# Environment_Sensor.net
KiCad netlist of a schematic drawn in EAGLE
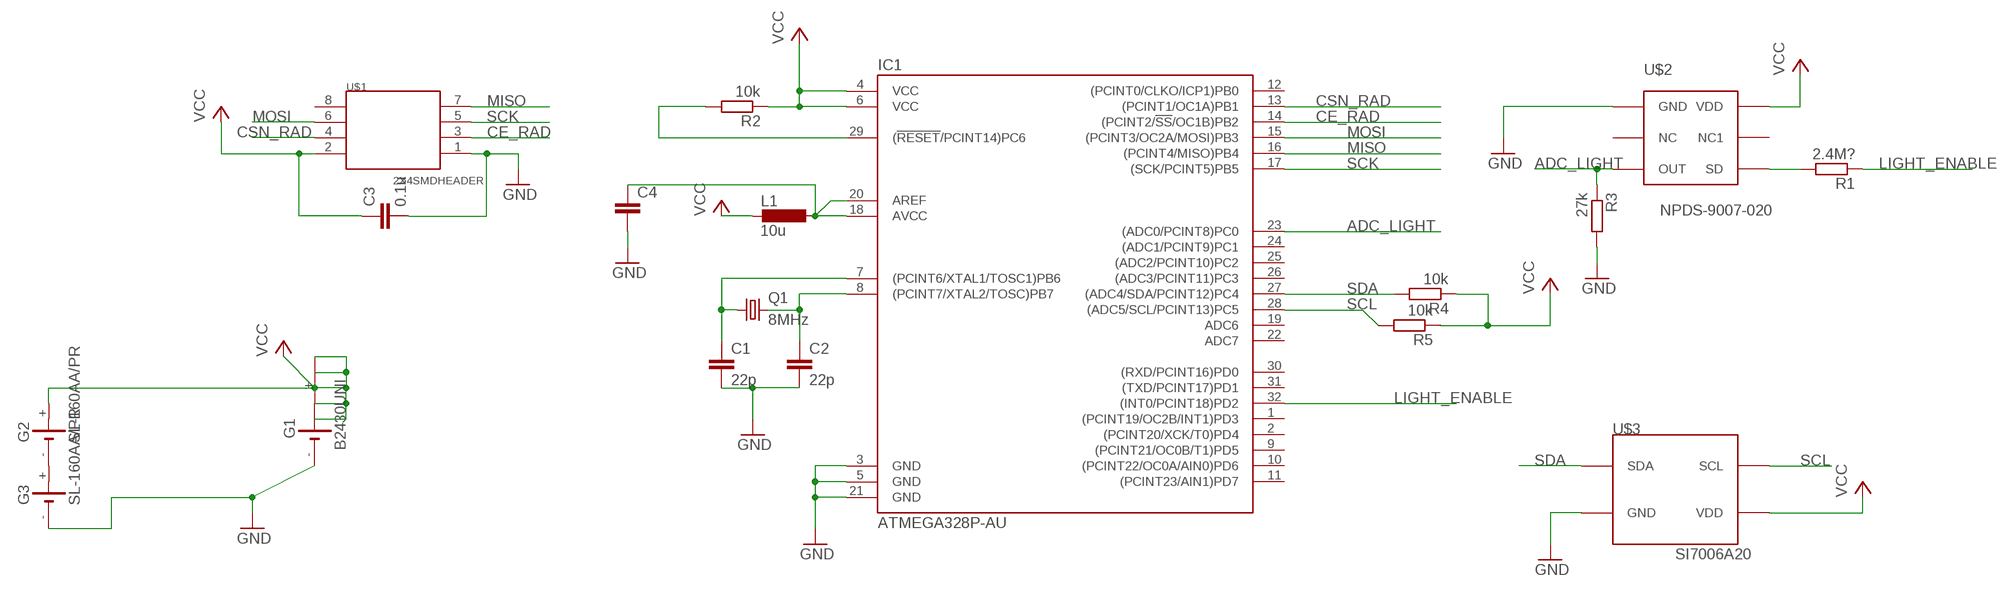
[diagram p0: schematic, sheet 1]

(export (version "E")
  (design (tool "Eeschema 10.0.6"))
  (components
    (comp (ref "C1")
      (value "22p")
      (footprint "eagle-import:C1206K")
      (libsource (lib "eagle-import") (part "C-EUC1206K"))
    )
    (comp (ref "C2")
      (value "22p")
      (footprint "eagle-import:C1206K")
      (libsource (lib "eagle-import") (part "C-EUC1206K"))
    )
    (comp (ref "C3")
      (value "0.1u")
      (footprint "eagle-import:C1206K")
      (libsource (lib "eagle-import") (part "C-EUC1206K"))
    )
    (comp (ref "C4")
      (value "C-EUC1206")
      (footprint "eagle-import:C1206")
      (libsource (lib "eagle-import") (part "C-EUC1206"))
    )
    (comp (ref "G1")
      (value "B2430UNI")
      (footprint "eagle-import:B2430UNI")
      (libsource (lib "eagle-import") (part "B2430UNI"))
    )
    (comp (ref "G2")
      (value "SL-160AA/PR")
      (footprint "eagle-import:SL-160AA_PR")
      (libsource (lib "eagle-import") (part "SL-160AA/PR"))
    )
    (comp (ref "G3")
      (value "SL-160AA/PR")
      (footprint "eagle-import:SL-160AA_PR")
      (libsource (lib "eagle-import") (part "SL-160AA/PR"))
    )
    (comp (ref "IC1")
      (value "ATMEGA328P-AU")
      (footprint "eagle-import:TQFP32-08")
      (libsource (lib "eagle-import") (part "ATMEGA328P-AU"))
    )
    (comp (ref "L1")
      (value "10u")
      (footprint "eagle-import:L3216C")
      (libsource (lib "eagle-import") (part "L-EUL3216C"))
    )
    (comp (ref "Q1")
      (value "8MHz")
      (footprint "eagle-import:HC49UP")
      (libsource (lib "eagle-import") (part "CRYSTALHC49UP"))
    )
    (comp (ref "R1")
      (value "2.4M?")
      (footprint "eagle-import:R1206")
      (libsource (lib "eagle-import") (part "R-EU_R1206"))
    )
    (comp (ref "R2")
      (value "10k")
      (footprint "eagle-import:R1206")
      (libsource (lib "eagle-import") (part "R-EU_R1206"))
    )
    (comp (ref "R3")
      (value "27k")
      (footprint "eagle-import:R1206")
      (libsource (lib "eagle-import") (part "R-EU_R1206"))
    )
    (comp (ref "R4")
      (value "10k")
      (footprint "eagle-import:R1206")
      (libsource (lib "eagle-import") (part "R-EU_R1206"))
    )
    (comp (ref "R5")
      (value "10k")
      (footprint "eagle-import:R1206")
      (libsource (lib "eagle-import") (part "R-EU_R1206"))
    )
    (comp (ref "U$1")
      (value "2X4SMDHEADER")
      (footprint "eagle-import:TSM-110-XX-XXX-DV")
      (libsource (lib "eagle-import") (part "2X4SMDHEADER"))
    )
    (comp (ref "U$2")
      (value "NPDS-9007-020")
      (footprint "eagle-import:APDS-9007")
      (libsource (lib "eagle-import") (part "NPDS-9007-020"))
    )
    (comp (ref "U$3")
      (value "SI7006A20")
      (footprint "eagle-import:3X3DFN")
      (libsource (lib "eagle-import") (part "SI7006A20"))
    )
  )
  (nets
    (net (code "1") (name "/ADC_LIGHT") (class "Default")
      (node (ref "IC1") (pin "23") (pinfunction "(ADC0/PCINT8)PC0_23") (pintype "bidirectional"))
      (node (ref "R3") (pin "1") (pinfunction "1_1") (pintype "passive"))
      (node (ref "U$2") (pin "P$3") (pinfunction "OUT_P$3") (pintype "bidirectional"))
    )
    (net (code "2") (name "/CE_RAD") (class "Default")
      (node (ref "IC1") (pin "14") (pinfunction "(PCINT2/~{SS}/OC1B)PB2_14") (pintype "bidirectional"))
      (node (ref "U$1") (pin "3") (pinfunction "3_3") (pintype "bidirectional"))
    )
    (net (code "3") (name "/CSN_RAD") (class "Default")
      (node (ref "IC1") (pin "13") (pinfunction "(PCINT1/OC1A)PB1_13") (pintype "bidirectional"))
      (node (ref "U$1") (pin "4") (pinfunction "4_4") (pintype "bidirectional"))
    )
    (net (code "4") (name "/LIGHT_ENABLE") (class "Default")
      (node (ref "IC1") (pin "32") (pinfunction "(INT0/PCINT18)PD2_32") (pintype "bidirectional"))
      (node (ref "R1") (pin "1") (pinfunction "1_1") (pintype "passive"))
    )
    (net (code "5") (name "/MISO") (class "Default")
      (node (ref "IC1") (pin "16") (pinfunction "(PCINT4/MISO)PB4_16") (pintype "bidirectional"))
      (node (ref "U$1") (pin "7") (pinfunction "7_7") (pintype "bidirectional"))
    )
    (net (code "6") (name "/MOSI") (class "Default")
      (node (ref "IC1") (pin "15") (pinfunction "(PCINT3/OC2A/MOSI)PB3_15") (pintype "bidirectional"))
      (node (ref "U$1") (pin "6") (pinfunction "6_6") (pintype "bidirectional"))
    )
    (net (code "7") (name "/SCK") (class "Default")
      (node (ref "IC1") (pin "17") (pinfunction "(SCK/PCINT5)PB5_17") (pintype "bidirectional"))
      (node (ref "U$1") (pin "5") (pinfunction "5_5") (pintype "bidirectional"))
    )
    (net (code "8") (name "/SCL") (class "Default")
      (node (ref "IC1") (pin "28") (pinfunction "(ADC5/SCL/PCINT13)PC5_28") (pintype "bidirectional"))
      (node (ref "R5") (pin "2") (pinfunction "2_2") (pintype "passive"))
      (node (ref "U$3") (pin "P$6") (pinfunction "SCL_P$6") (pintype "bidirectional"))
    )
    (net (code "9") (name "/SDA") (class "Default")
      (node (ref "IC1") (pin "27") (pinfunction "(ADC4/SDA/PCINT12)PC4_27") (pintype "bidirectional"))
      (node (ref "R4") (pin "2") (pinfunction "2_2") (pintype "passive"))
      (node (ref "U$3") (pin "P$1") (pinfunction "SDA_P$1") (pintype "bidirectional"))
    )
    (net (code "10") (name "GND") (class "Default")
      (node (ref "C1") (pin "2") (pinfunction "2_2") (pintype "passive"))
      (node (ref "C2") (pin "2") (pinfunction "2_2") (pintype "passive"))
      (node (ref "C3") (pin "2") (pinfunction "2_2") (pintype "passive"))
      (node (ref "C4") (pin "2") (pinfunction "2_2") (pintype "passive"))
      (node (ref "G1") (pin "-") (pinfunction "-_-") (pintype "passive"))
      (node (ref "G3") (pin "-") (pinfunction "-_-") (pintype "passive"))
      (node (ref "IC1") (pin "21") (pinfunction "GND_21") (pintype "bidirectional"))
      (node (ref "IC1") (pin "3") (pinfunction "GND_3") (pintype "bidirectional"))
      (node (ref "IC1") (pin "5") (pinfunction "GND_5") (pintype "bidirectional"))
      (node (ref "R3") (pin "2") (pinfunction "2_2") (pintype "passive"))
      (node (ref "U$1") (pin "1") (pinfunction "1_1") (pintype "bidirectional"))
      (node (ref "U$2") (pin "P$1") (pinfunction "GND_P$1") (pintype "bidirectional"))
      (node (ref "U$3") (pin "P$2") (pinfunction "GND_P$2") (pintype "bidirectional"))
    )
    (net (code "11") (name "Net-(G2-Pad-)") (class "Default")
      (node (ref "G2") (pin "-") (pinfunction "-_-") (pintype "passive"))
      (node (ref "G3") (pin "+") (pinfunction "+_+") (pintype "passive"))
    )
    (net (code "12") (name "Net-(IC1-(PCINT6{slash}XTAL1{slash}TOSC1)PB6)") (class "Default")
      (node (ref "C1") (pin "1") (pinfunction "1_1") (pintype "passive"))
      (node (ref "IC1") (pin "7") (pinfunction "(PCINT6/XTAL1/TOSC1)PB6_7") (pintype "bidirectional"))
      (node (ref "Q1") (pin "1") (pinfunction "1_1") (pintype "passive"))
    )
    (net (code "13") (name "Net-(IC1-(PCINT7{slash}XTAL2{slash}TOSC)PB7)") (class "Default")
      (node (ref "C2") (pin "1") (pinfunction "1_1") (pintype "passive"))
      (node (ref "IC1") (pin "8") (pinfunction "(PCINT7/XTAL2/TOSC)PB7_8") (pintype "bidirectional"))
      (node (ref "Q1") (pin "2") (pinfunction "2_2") (pintype "passive"))
    )
    (net (code "14") (name "Net-(IC1-(~{RESET}{slash}PCINT14)PC6)") (class "Default")
      (node (ref "IC1") (pin "29") (pinfunction "(~{RESET}/PCINT14)PC6_29") (pintype "bidirectional"))
      (node (ref "R2") (pin "2") (pinfunction "2_2") (pintype "passive"))
    )
    (net (code "15") (name "Net-(IC1-AREF)") (class "Default")
      (node (ref "C4") (pin "1") (pinfunction "1_1") (pintype "passive"))
      (node (ref "IC1") (pin "18") (pinfunction "AVCC_18") (pintype "bidirectional"))
      (node (ref "IC1") (pin "20") (pinfunction "AREF_20") (pintype "bidirectional"))
      (node (ref "L1") (pin "1") (pinfunction "1_1") (pintype "passive"))
    )
    (net (code "16") (name "Net-(U$2-SD)") (class "Default")
      (node (ref "R1") (pin "2") (pinfunction "2_2") (pintype "passive"))
      (node (ref "U$2") (pin "P$6") (pinfunction "SD_P$6") (pintype "bidirectional"))
    )
    (net (code "17") (name "VCC") (class "Default")
      (node (ref "C3") (pin "1") (pinfunction "1_1") (pintype "passive"))
      (node (ref "G1") (pin "+") (pinfunction "+_+") (pintype "passive"))
      (node (ref "G1") (pin "+@1") (pinfunction "+_+@1") (pintype "passive"))
      (node (ref "G1") (pin "+@2") (pinfunction "+_+@2") (pintype "passive"))
      (node (ref "G1") (pin "+@3") (pinfunction "+_+@3") (pintype "passive"))
      (node (ref "G1") (pin "+@4") (pinfunction "+_+@4") (pintype "passive"))
      (node (ref "G2") (pin "+") (pinfunction "+_+") (pintype "passive"))
      (node (ref "IC1") (pin "4") (pinfunction "VCC_4") (pintype "bidirectional"))
      (node (ref "IC1") (pin "6") (pinfunction "VCC_6") (pintype "bidirectional"))
      (node (ref "L1") (pin "2") (pinfunction "2_2") (pintype "passive"))
      (node (ref "R2") (pin "1") (pinfunction "1_1") (pintype "passive"))
      (node (ref "R4") (pin "1") (pinfunction "1_1") (pintype "passive"))
      (node (ref "R5") (pin "1") (pinfunction "1_1") (pintype "passive"))
      (node (ref "U$1") (pin "2") (pinfunction "2_2") (pintype "bidirectional"))
      (node (ref "U$2") (pin "P$4") (pinfunction "VDD_P$4") (pintype "bidirectional"))
      (node (ref "U$3") (pin "P$5") (pinfunction "VDD_P$5") (pintype "bidirectional"))
    )
    (net (code "18") (name "unconnected-(G1---Pad-@1)") (class "Default")
      (node (ref "G1") (pin "-@1") (pinfunction "-_-@1") (pintype "passive"))
    )
    (net (code "19") (name "unconnected-(IC1-(ADC1{slash}PCINT9)PC1-Pad24)") (class "Default")
      (node (ref "IC1") (pin "24") (pinfunction "(ADC1/PCINT9)PC1_24") (pintype "bidirectional"))
    )
    (net (code "20") (name "unconnected-(IC1-(ADC2{slash}PCINT10)PC2-Pad25)") (class "Default")
      (node (ref "IC1") (pin "25") (pinfunction "(ADC2/PCINT10)PC2_25") (pintype "bidirectional"))
    )
    (net (code "21") (name "unconnected-(IC1-(ADC3{slash}PCINT11)PC3-Pad26)") (class "Default")
      (node (ref "IC1") (pin "26") (pinfunction "(ADC3/PCINT11)PC3_26") (pintype "bidirectional"))
    )
    (net (code "22") (name "unconnected-(IC1-(PCINT0{slash}CLKO{slash}ICP1)PB0-Pad12)") (class "Default")
      (node (ref "IC1") (pin "12") (pinfunction "(PCINT0/CLKO/ICP1)PB0_12") (pintype "bidirectional"))
    )
    (net (code "23") (name "unconnected-(IC1-(PCINT19{slash}OC2B{slash}INT1)PD3-Pad1)") (class "Default")
      (node (ref "IC1") (pin "1") (pinfunction "(PCINT19/OC2B/INT1)PD3_1") (pintype "bidirectional"))
    )
    (net (code "24") (name "unconnected-(IC1-(PCINT20{slash}XCK{slash}T0)PD4-Pad2)") (class "Default")
      (node (ref "IC1") (pin "2") (pinfunction "(PCINT20/XCK/T0)PD4_2") (pintype "bidirectional"))
    )
    (net (code "25") (name "unconnected-(IC1-(PCINT21{slash}OC0B{slash}T1)PD5-Pad9)") (class "Default")
      (node (ref "IC1") (pin "9") (pinfunction "(PCINT21/OC0B/T1)PD5_9") (pintype "bidirectional"))
    )
    (net (code "26") (name "unconnected-(IC1-(PCINT22{slash}OC0A{slash}AIN0)PD6-Pad10)") (class "Default")
      (node (ref "IC1") (pin "10") (pinfunction "(PCINT22/OC0A/AIN0)PD6_10") (pintype "bidirectional"))
    )
    (net (code "27") (name "unconnected-(IC1-(PCINT23{slash}AIN1)PD7-Pad11)") (class "Default")
      (node (ref "IC1") (pin "11") (pinfunction "(PCINT23/AIN1)PD7_11") (pintype "bidirectional"))
    )
    (net (code "28") (name "unconnected-(IC1-(RXD{slash}PCINT16)PD0-Pad30)") (class "Default")
      (node (ref "IC1") (pin "30") (pinfunction "(RXD/PCINT16)PD0_30") (pintype "bidirectional"))
    )
    (net (code "29") (name "unconnected-(IC1-(TXD{slash}PCINT17)PD1-Pad31)") (class "Default")
      (node (ref "IC1") (pin "31") (pinfunction "(TXD/PCINT17)PD1_31") (pintype "bidirectional"))
    )
    (net (code "30") (name "unconnected-(IC1-ADC6-Pad19)") (class "Default")
      (node (ref "IC1") (pin "19") (pinfunction "ADC6_19") (pintype "bidirectional"))
    )
    (net (code "31") (name "unconnected-(IC1-ADC7-Pad22)") (class "Default")
      (node (ref "IC1") (pin "22") (pinfunction "ADC7_22") (pintype "bidirectional"))
    )
    (net (code "32") (name "unconnected-(U$1-Pad8)") (class "Default")
      (node (ref "U$1") (pin "8") (pinfunction "8_8") (pintype "bidirectional"))
    )
    (net (code "33") (name "unconnected-(U$2-NC-PadP$2)") (class "Default")
      (node (ref "U$2") (pin "P$2") (pinfunction "NC_P$2") (pintype "no_connect"))
    )
    (net (code "34") (name "unconnected-(U$2-NC1-PadP$5)") (class "Default")
      (node (ref "U$2") (pin "P$5") (pinfunction "NC1_P$5") (pintype "no_connect"))
    )
  )
)
